# 1_Esp32.net
KiCad netlist of a schematic drawn in Altium Designer
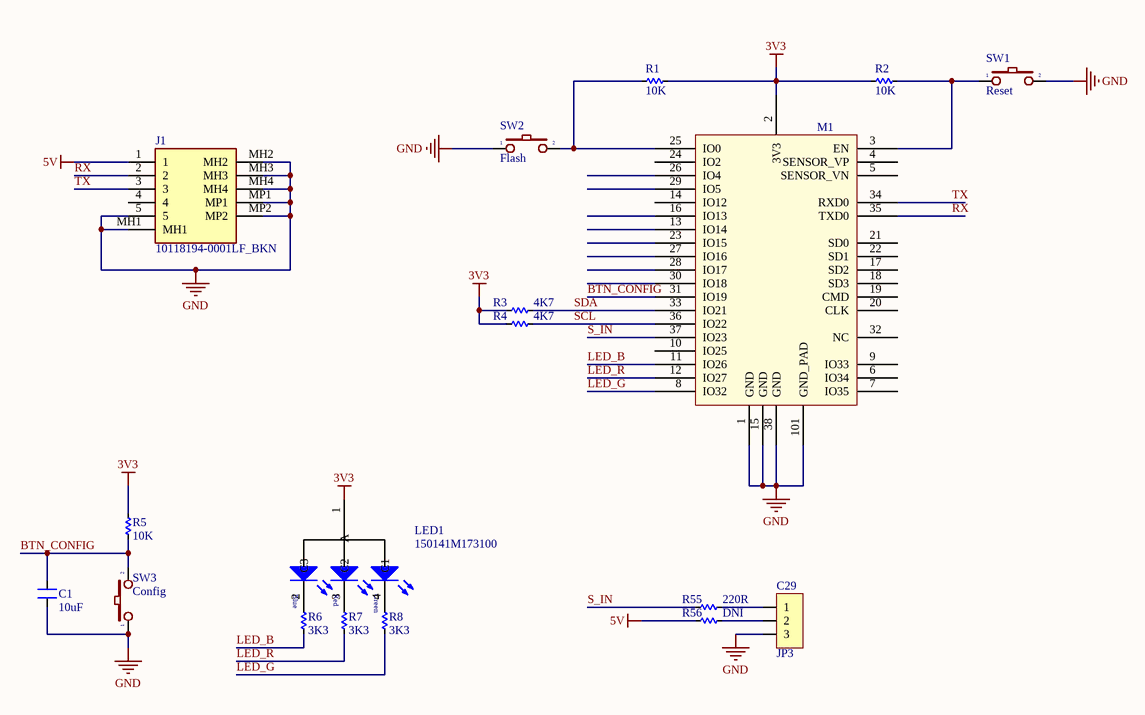
[diagram p0: [1]Esp32.SchDoc]

(export (version "E")
  (design (tool "Eeschema 10.0.6"))
  (components
    (comp (ref "C1")
      (value "10uF")
      (footprint "CN-SMD-0603")
      (description "Tu gom")
      (libsource (lib "LIBTanCN") (part "CN"))
    )
    (comp (ref "C29")
      (value "JP3")
      (footprint "JP3-D1C")
      (description "WR-PHD 2.54 mm Angled Socket Header")
      (fields
        (field (name "MANUFACTURER") "Würth Elektronik eiSos GmbH")
        (field (name "PARTNO") "613003143121")
        (field (name "CREATED BY") "Karrer Zheng")
      )
      (libsource (lib "LIBRARY") (part "JP3"))
    )
    (comp (ref "J1")
      (value "10118194-0001LF_BKN")
      (footprint "SamacSys:101181940001LFBKN")
      (description "Connector")
      (fields (field (name "MANUFACTURER_PART_NUMBER") "10118194-0001LF/BKN"))
      (libsource (lib "*") (part "10118194-0001LF_BKN"))
    )
    (comp (ref "LED1")
      (value "150141M173100")
      (footprint "LED RGB 3528")
      (description "SMD Full-Color Top LED, WL-SFTW, Red & Green & Blue")
      (fields
        (field (name "MANUFACTURER") "Würth Elektronik eiSos GmbH")
        (field (name "CREATED BY") "Christin Otto")
      )
      (libsource (lib "LIBRARY") (part "LED RGB SMD"))
    )
    (comp (ref "M1")
      (value "ESP32S_Module")
      (footprint "ESP32S")
      (description "Esp-32S")
      (libsource (lib "ESP32S") (part "ESP32S_Module"))
    )
    (comp (ref "R1")
      (value "10K")
      (footprint "RES-SMD-0603")
      (description "Resistor")
      (fields
        (field (name "MANUFACTURER") "Generic Components")
        (field (name "PUBLISHER") "Altium Hobart Technology Centre")
      )
      (libsource (lib "LIBRARY") (part "Res-SMD"))
    )
    (comp (ref "R2")
      (value "10K")
      (footprint "RES-SMD-0603")
      (description "Resistor")
      (fields
        (field (name "MANUFACTURER") "Generic Components")
        (field (name "PUBLISHER") "Altium Hobart Technology Centre")
      )
      (libsource (lib "LIBRARY") (part "Res-SMD"))
    )
    (comp (ref "R3")
      (value "4K7")
      (footprint "RES-SMD-0603")
      (description "Resistor")
      (fields
        (field (name "MANUFACTURER") "Generic Components")
        (field (name "PUBLISHER") "Altium Hobart Technology Centre")
      )
      (libsource (lib "LIBRARY") (part "Res-SMD"))
    )
    (comp (ref "R4")
      (value "4K7")
      (footprint "RES-SMD-0603")
      (description "Resistor")
      (fields
        (field (name "MANUFACTURER") "Generic Components")
        (field (name "PUBLISHER") "Altium Hobart Technology Centre")
      )
      (libsource (lib "LIBRARY") (part "Res-SMD"))
    )
    (comp (ref "R5")
      (value "10K")
      (footprint "RES-SMD-0603")
      (description "Resistor")
      (fields
        (field (name "MANUFACTURER") "Generic Components")
        (field (name "PUBLISHER") "Altium Hobart Technology Centre")
      )
      (libsource (lib "LIBRARY") (part "Res-SMD"))
    )
    (comp (ref "R6")
      (value "3K3")
      (footprint "RES-SMD-0603")
      (description "Resistor")
      (fields
        (field (name "MANUFACTURER") "Generic Components")
        (field (name "PUBLISHER") "Altium Hobart Technology Centre")
      )
      (libsource (lib "LIBRARY") (part "Res-SMD"))
    )
    (comp (ref "R7")
      (value "3K3")
      (footprint "RES-SMD-0603")
      (description "Resistor")
      (fields
        (field (name "MANUFACTURER") "Generic Components")
        (field (name "PUBLISHER") "Altium Hobart Technology Centre")
      )
      (libsource (lib "LIBRARY") (part "Res-SMD"))
    )
    (comp (ref "R8")
      (value "3K3")
      (footprint "RES-SMD-0603")
      (description "Resistor")
      (fields
        (field (name "MANUFACTURER") "Generic Components")
        (field (name "PUBLISHER") "Altium Hobart Technology Centre")
      )
      (libsource (lib "LIBRARY") (part "Res-SMD"))
    )
    (comp (ref "R55")
      (value "220R")
      (footprint "RES-SMD-0603")
      (description "Resistor")
      (fields
        (field (name "MANUFACTURER") "Generic Components")
        (field (name "PUBLISHER") "Altium Hobart Technology Centre")
      )
      (libsource (lib "LIBRARY") (part "Res-SMD"))
    )
    (comp (ref "R56")
      (value "DNI")
      (footprint "RES-SMD-0603")
      (description "Resistor")
      (fields
        (field (name "MANUFACTURER") "Generic Components")
        (field (name "PUBLISHER") "Altium Hobart Technology Centre")
      )
      (libsource (lib "LIBRARY") (part "Res-SMD"))
    )
    (comp (ref "SW1")
      (value "Reset")
      (footprint "SW1-SMD")
      (description "Switch button 2 pin")
      (libsource (lib "LIBRARY") (part "SW2"))
    )
    (comp (ref "SW2")
      (value "Flash")
      (footprint "SW-DIP1-1")
      (description "Switch button 2 pin")
      (libsource (lib "LIBRARY") (part "SW2"))
    )
    (comp (ref "SW3")
      (value "Config")
      (footprint "SW1-SMD")
      (description "Switch button 2 pin")
      (libsource (lib "LIBRARY") (part "SW2"))
    )
  )
  (nets
    (net (code "1") (name "/BTN_CONFIG") (class "Default")
      (node (ref "C1") (pin "1") (pinfunction "1_1") (pintype "passive"))
      (node (ref "M1") (pin "31") (pinfunction "IO19_31") (pintype "passive"))
      (node (ref "R5") (pin "1") (pinfunction "1_1") (pintype "passive"))
      (node (ref "SW3") (pin "2") (pinfunction "2_2") (pintype "passive"))
    )
    (net (code "2") (name "/LED_B") (class "Default")
      (node (ref "M1") (pin "11") (pinfunction "IO26_11") (pintype "passive"))
      (node (ref "R6") (pin "1") (pinfunction "1_1") (pintype "passive"))
    )
    (net (code "3") (name "/LED_G") (class "Default")
      (node (ref "M1") (pin "8") (pinfunction "IO32_8") (pintype "passive"))
      (node (ref "R8") (pin "1") (pinfunction "1_1") (pintype "passive"))
    )
    (net (code "4") (name "/LED_R") (class "Default")
      (node (ref "M1") (pin "12") (pinfunction "IO27_12") (pintype "passive"))
      (node (ref "R7") (pin "1") (pinfunction "1_1") (pintype "passive"))
    )
    (net (code "5") (name "/RX") (class "Default")
      (node (ref "J1") (pin "2") (pinfunction "2_2") (pintype "passive"))
      (node (ref "M1") (pin "35") (pinfunction "TXD0_35") (pintype "passive"))
    )
    (net (code "6") (name "/SCL") (class "Default")
      (node (ref "M1") (pin "36") (pinfunction "IO22_36") (pintype "passive"))
      (node (ref "R4") (pin "2") (pinfunction "2_2") (pintype "passive"))
    )
    (net (code "7") (name "/SDA") (class "Default")
      (node (ref "M1") (pin "33") (pinfunction "IO21_33") (pintype "passive"))
      (node (ref "R3") (pin "2") (pinfunction "2_2") (pintype "passive"))
    )
    (net (code "8") (name "/S_IN") (class "Default")
      (node (ref "M1") (pin "37") (pinfunction "IO23_37") (pintype "passive"))
      (node (ref "R55") (pin "2") (pinfunction "2_2") (pintype "passive"))
    )
    (net (code "9") (name "/TX") (class "Default")
      (node (ref "J1") (pin "3") (pinfunction "3_3") (pintype "passive"))
      (node (ref "M1") (pin "34") (pinfunction "RXD0_34") (pintype "passive"))
    )
    (net (code "10") (name "3V3") (class "Default")
      (node (ref "LED1") (pin "1") (pinfunction "A_1") (pintype "passive"))
      (node (ref "M1") (pin "2") (pinfunction "3V3_2") (pintype "power_in"))
      (node (ref "R1") (pin "1") (pinfunction "1_1") (pintype "passive"))
      (node (ref "R2") (pin "2") (pinfunction "2_2") (pintype "passive"))
      (node (ref "R3") (pin "1") (pinfunction "1_1") (pintype "passive"))
      (node (ref "R4") (pin "1") (pinfunction "1_1") (pintype "passive"))
      (node (ref "R5") (pin "2") (pinfunction "2_2") (pintype "passive"))
    )
    (net (code "11") (name "5V") (class "Default")
      (node (ref "J1") (pin "1") (pinfunction "1_1") (pintype "passive"))
      (node (ref "R56") (pin "2") (pinfunction "2_2") (pintype "passive"))
    )
    (net (code "12") (name "GND") (class "Default")
      (node (ref "C1") (pin "2") (pinfunction "2_2") (pintype "passive"))
      (node (ref "C29") (pin "3") (pinfunction "3_3") (pintype "passive"))
      (node (ref "J1") (pin "5") (pinfunction "5_5") (pintype "passive"))
      (node (ref "J1") (pin "MH1") (pinfunction "MH1_MH1") (pintype "passive"))
      (node (ref "J1") (pin "MH2") (pinfunction "MH2_MH2") (pintype "passive"))
      (node (ref "J1") (pin "MH3") (pinfunction "MH3_MH3") (pintype "passive"))
      (node (ref "J1") (pin "MH4") (pinfunction "MH4_MH4") (pintype "passive"))
      (node (ref "J1") (pin "MP1") (pinfunction "MP1_MP1") (pintype "passive"))
      (node (ref "J1") (pin "MP2") (pinfunction "MP2_MP2") (pintype "passive"))
      (node (ref "M1") (pin "1") (pinfunction "GND_1") (pintype "power_in"))
      (node (ref "M1") (pin "101") (pinfunction "GND_PAD_101") (pintype "power_in"))
      (node (ref "M1") (pin "15") (pinfunction "GND_15") (pintype "power_in"))
      (node (ref "M1") (pin "38") (pinfunction "GND_38") (pintype "power_in"))
      (node (ref "SW1") (pin "2") (pinfunction "2_2") (pintype "passive"))
      (node (ref "SW2") (pin "1") (pinfunction "1_1") (pintype "passive"))
      (node (ref "SW3") (pin "1") (pinfunction "1_1") (pintype "passive"))
    )
    (net (code "13") (name "Net-(C29-Pad1)") (class "Default")
      (node (ref "C29") (pin "1") (pinfunction "1_1") (pintype "passive"))
      (node (ref "R55") (pin "1") (pinfunction "1_1") (pintype "passive"))
    )
    (net (code "14") (name "Net-(C29-Pad2)") (class "Default")
      (node (ref "C29") (pin "2") (pinfunction "2_2") (pintype "passive"))
      (node (ref "R56") (pin "1") (pinfunction "1_1") (pintype "passive"))
    )
    (net (code "15") (name "Net-(LED1-C1)") (class "Default")
      (node (ref "LED1") (pin "4") (pinfunction "C1_4") (pintype "passive"))
      (node (ref "R8") (pin "2") (pinfunction "2_2") (pintype "passive"))
    )
    (net (code "16") (name "Net-(LED1-C2)") (class "Default")
      (node (ref "LED1") (pin "3") (pinfunction "C2_3") (pintype "passive"))
      (node (ref "R7") (pin "2") (pinfunction "2_2") (pintype "passive"))
    )
    (net (code "17") (name "Net-(LED1-C3)") (class "Default")
      (node (ref "LED1") (pin "2") (pinfunction "C3_2") (pintype "passive"))
      (node (ref "R6") (pin "2") (pinfunction "2_2") (pintype "passive"))
    )
    (net (code "18") (name "Net-(M1-EN)") (class "Default")
      (node (ref "M1") (pin "3") (pinfunction "EN_3") (pintype "power_in"))
      (node (ref "R2") (pin "1") (pinfunction "1_1") (pintype "passive"))
      (node (ref "SW1") (pin "1") (pinfunction "1_1") (pintype "passive"))
    )
    (net (code "19") (name "Net-(M1-IO0)") (class "Default")
      (node (ref "M1") (pin "25") (pinfunction "IO0_25") (pintype "passive"))
      (node (ref "R1") (pin "2") (pinfunction "2_2") (pintype "passive"))
      (node (ref "SW2") (pin "2") (pinfunction "2_2") (pintype "passive"))
    )
    (net (code "20") (name "unconnected-(J1-Pad4)") (class "Default")
      (node (ref "J1") (pin "4") (pinfunction "4_4") (pintype "passive"))
    )
    (net (code "21") (name "unconnected-(M1-CLK-Pad20)") (class "Default")
      (node (ref "M1") (pin "20") (pinfunction "CLK_20") (pintype "passive"))
    )
    (net (code "22") (name "unconnected-(M1-CMD-Pad19)") (class "Default")
      (node (ref "M1") (pin "19") (pinfunction "CMD_19") (pintype "passive"))
    )
    (net (code "23") (name "unconnected-(M1-IO2-Pad24)") (class "Default")
      (node (ref "M1") (pin "24") (pinfunction "IO2_24") (pintype "passive"))
    )
    (net (code "24") (name "unconnected-(M1-IO4-Pad26)") (class "Default")
      (node (ref "M1") (pin "26") (pinfunction "IO4_26") (pintype "passive"))
    )
    (net (code "25") (name "unconnected-(M1-IO5-Pad29)") (class "Default")
      (node (ref "M1") (pin "29") (pinfunction "IO5_29") (pintype "passive"))
    )
    (net (code "26") (name "unconnected-(M1-IO12-Pad14)") (class "Default")
      (node (ref "M1") (pin "14") (pinfunction "IO12_14") (pintype "passive"))
    )
    (net (code "27") (name "unconnected-(M1-IO13-Pad16)") (class "Default")
      (node (ref "M1") (pin "16") (pinfunction "IO13_16") (pintype "passive"))
    )
    (net (code "28") (name "unconnected-(M1-IO14-Pad13)") (class "Default")
      (node (ref "M1") (pin "13") (pinfunction "IO14_13") (pintype "passive"))
    )
    (net (code "29") (name "unconnected-(M1-IO15-Pad23)") (class "Default")
      (node (ref "M1") (pin "23") (pinfunction "IO15_23") (pintype "passive"))
    )
    (net (code "30") (name "unconnected-(M1-IO16-Pad27)") (class "Default")
      (node (ref "M1") (pin "27") (pinfunction "IO16_27") (pintype "passive"))
    )
    (net (code "31") (name "unconnected-(M1-IO17-Pad28)") (class "Default")
      (node (ref "M1") (pin "28") (pinfunction "IO17_28") (pintype "passive"))
    )
    (net (code "32") (name "unconnected-(M1-IO18-Pad30)") (class "Default")
      (node (ref "M1") (pin "30") (pinfunction "IO18_30") (pintype "passive"))
    )
    (net (code "33") (name "unconnected-(M1-IO25-Pad10)") (class "Default")
      (node (ref "M1") (pin "10") (pinfunction "IO25_10") (pintype "passive"))
    )
    (net (code "34") (name "unconnected-(M1-IO33-Pad9)") (class "Default")
      (node (ref "M1") (pin "9") (pinfunction "IO33_9") (pintype "passive"))
    )
    (net (code "35") (name "unconnected-(M1-IO34-Pad6)") (class "Default")
      (node (ref "M1") (pin "6") (pinfunction "IO34_6") (pintype "passive"))
    )
    (net (code "36") (name "unconnected-(M1-IO35-Pad7)") (class "Default")
      (node (ref "M1") (pin "7") (pinfunction "IO35_7") (pintype "passive"))
    )
    (net (code "37") (name "unconnected-(M1-NC-Pad32)") (class "Default")
      (node (ref "M1") (pin "32") (pinfunction "NC_32") (pintype "passive"))
    )
    (net (code "38") (name "unconnected-(M1-SD0-Pad21)") (class "Default")
      (node (ref "M1") (pin "21") (pinfunction "SD0_21") (pintype "passive"))
    )
    (net (code "39") (name "unconnected-(M1-SD1-Pad22)") (class "Default")
      (node (ref "M1") (pin "22") (pinfunction "SD1_22") (pintype "passive"))
    )
    (net (code "40") (name "unconnected-(M1-SD2-Pad17)") (class "Default")
      (node (ref "M1") (pin "17") (pinfunction "SD2_17") (pintype "passive"))
    )
    (net (code "41") (name "unconnected-(M1-SD3-Pad18)") (class "Default")
      (node (ref "M1") (pin "18") (pinfunction "SD3_18") (pintype "passive"))
    )
    (net (code "42") (name "unconnected-(M1-SENSOR_VN-Pad5)") (class "Default")
      (node (ref "M1") (pin "5") (pinfunction "SENSOR_VN_5") (pintype "passive"))
    )
    (net (code "43") (name "unconnected-(M1-SENSOR_VP-Pad4)") (class "Default")
      (node (ref "M1") (pin "4") (pinfunction "SENSOR_VP_4") (pintype "passive"))
    )
  )
)
